# ESQUEMATICO.net
KiCad netlist of a schematic drawn in Altium Designer
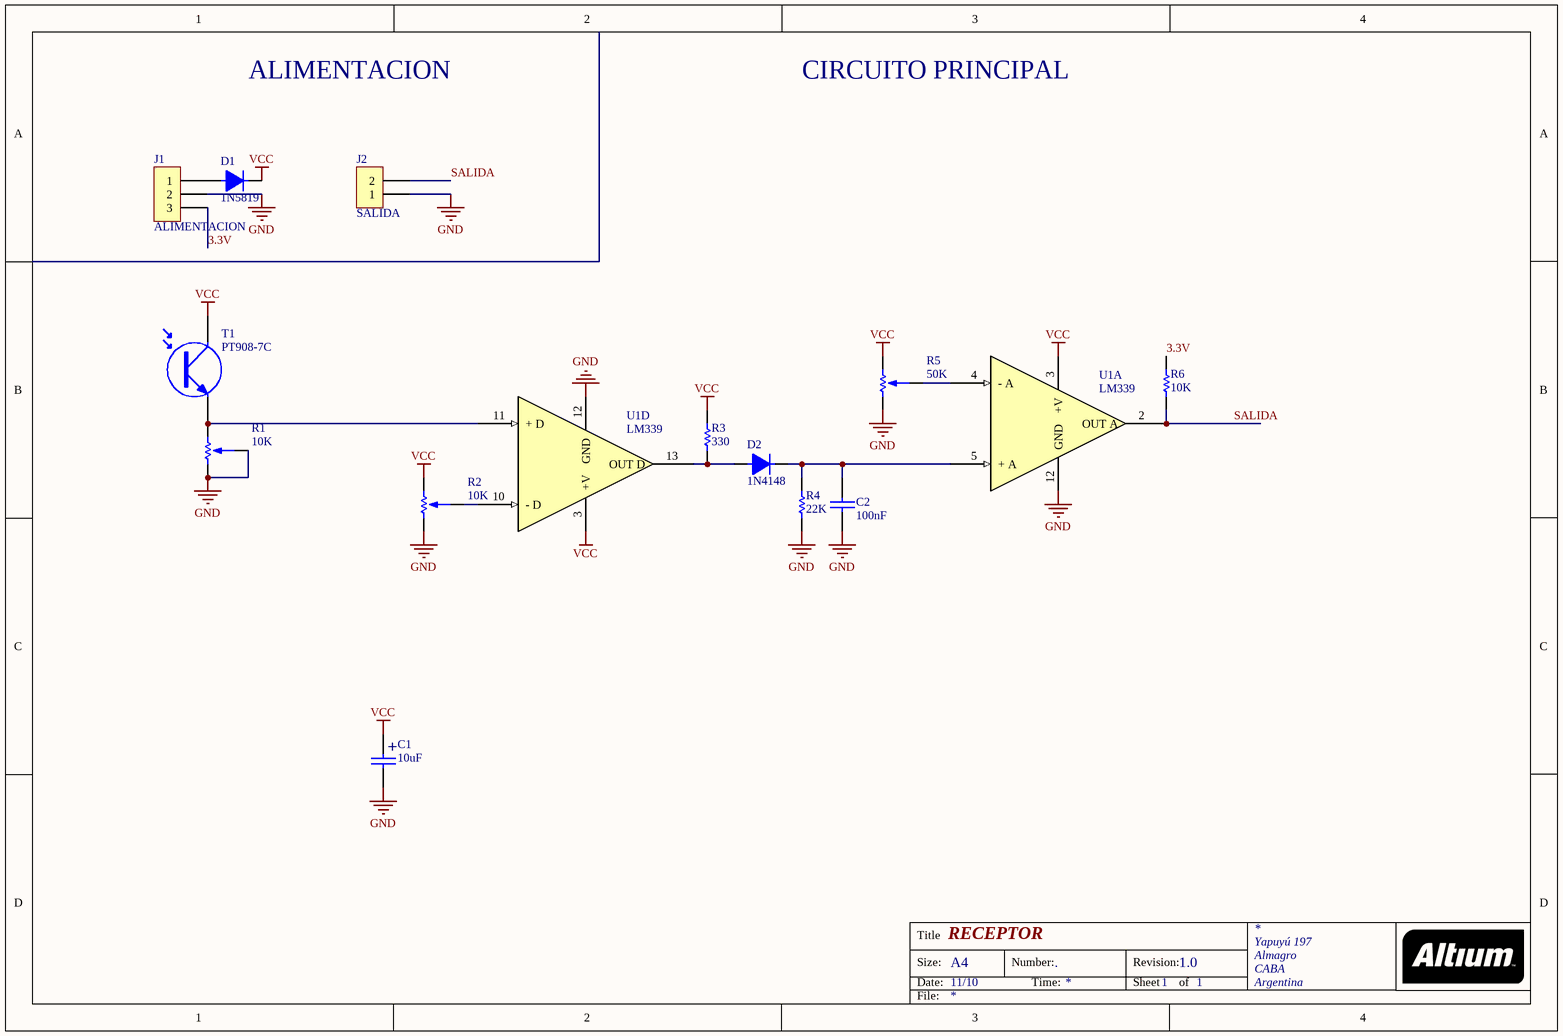
[diagram p0: ESQUEMATICO.SchDoc]

(export (version "E")
  (design (tool "Eeschema 10.0.6"))
  (components
    (comp (ref "C1") (value "10uF") (footprint "CAP100RP") (libsource (lib "LIB-PIO-IX") (part "CAPPOL")))
    (comp (ref "C2") (value "100nF") (footprint "CAP200") (libsource (lib "Libreria4") (part "CAP")))
    (comp (ref "D1") (value "1N5819") (footprint "DO41") (libsource (lib "Libreria4") (part "DIODO")))
    (comp (ref "D2") (value "1N4148") (footprint "DO41") (libsource (lib "Libreria4") (part "DIODO")))
    (comp (ref "J1")
      (value "ALIMENTACION")
      (footprint "BORNERA3")
      (libsource (lib "LIBEBAL") (part "BORNERA 3"))
    )
    (comp (ref "J2") (value "SALIDA") (footprint "BORNERA2") (libsource (lib "Libreria4") (part "BORNERA 2")))
    (comp (ref "R1") (value "10K") (footprint "PRESET V") (libsource (lib "Libreria4") (part "PRESET")))
    (comp (ref "R2") (value "10K") (footprint "PRESET V") (libsource (lib "Libreria4") (part "PRESET")))
    (comp (ref "R3") (value "330") (footprint "RES400") (libsource (lib "Libreria4") (part "RES")))
    (comp (ref "R4") (value "22K") (footprint "RES400") (libsource (lib "Libreria4") (part "RES")))
    (comp (ref "R5") (value "50K") (footprint "PRESET V") (libsource (lib "Libreria4") (part "PRESET")))
    (comp (ref "R6") (value "10K") (footprint "RES400") (libsource (lib "LIBEBAL") (part "RES")))
    (comp (ref "T1")
      (value "PT908-7C")
      (footprint "pototransistor")
      (description "fototransistor")
      (libsource (lib "Libreria4") (part "PT908-7C"))
    )
    (comp (ref "U1")
      (value "LM339")
      (footprint "DIP14")
      (description "Comparador Open Collector")
      (libsource (lib "Libreria4") (part "LM339"))
    )
  )
  (nets
    (net (code "1") (name "/3.3V") (class "Default")
      (node (ref "J1") (pin "3") (pinfunction "3_3") (pintype "passive"))
      (node (ref "R6") (pin "2") (pinfunction "2_2") (pintype "passive"))
    )
    (net (code "2") (name "/SALIDA") (class "Default")
      (node (ref "J2") (pin "2") (pinfunction "2_2") (pintype "passive"))
      (node (ref "R6") (pin "1") (pinfunction "1_1") (pintype "passive"))
      (node (ref "U1") (pin "2") (pinfunction "OUT_A_2") (pintype "open_collector"))
    )
    (net (code "3") (name "GND") (class "Default")
      (node (ref "C1") (pin "2") (pinfunction "2_2") (pintype "passive"))
      (node (ref "C2") (pin "2") (pinfunction "2_2") (pintype "passive"))
      (node (ref "J1") (pin "2") (pinfunction "2_2") (pintype "passive"))
      (node (ref "J2") (pin "1") (pinfunction "1_1") (pintype "passive"))
      (node (ref "R1") (pin "2") (pinfunction "2_2") (pintype "passive"))
      (node (ref "R1") (pin "3") (pinfunction "3_3") (pintype "passive"))
      (node (ref "R2") (pin "3") (pinfunction "3_3") (pintype "passive"))
      (node (ref "R4") (pin "1") (pinfunction "1_1") (pintype "passive"))
      (node (ref "R5") (pin "3") (pinfunction "3_3") (pintype "passive"))
      (node (ref "U1") (pin "12") (pinfunction "GND_12") (pintype "passive"))
    )
    (net (code "4") (name "Net-(D1-Pad1)") (class "Default")
      (node (ref "D1") (pin "1") (pinfunction "1_1") (pintype "passive"))
      (node (ref "J1") (pin "1") (pinfunction "1_1") (pintype "passive"))
    )
    (net (code "5") (name "Net-(T1-E)") (class "Default")
      (node (ref "R1") (pin "1") (pinfunction "1_1") (pintype "passive"))
      (node (ref "T1") (pin "1") (pinfunction "E_1") (pintype "passive"))
      (node (ref "U1") (pin "11") (pinfunction "+_D_11") (pintype "input"))
    )
    (net (code "6") (name "Net-(U1A-+_A)") (class "Default")
      (node (ref "C2") (pin "1") (pinfunction "1_1") (pintype "passive"))
      (node (ref "D2") (pin "2") (pinfunction "2_2") (pintype "passive"))
      (node (ref "R4") (pin "2") (pinfunction "2_2") (pintype "passive"))
      (node (ref "U1") (pin "5") (pinfunction "+_A_5") (pintype "input"))
    )
    (net (code "7") (name "Net-(U1A--_A)") (class "Default")
      (node (ref "R5") (pin "2") (pinfunction "2_2") (pintype "passive"))
      (node (ref "U1") (pin "4") (pinfunction "-_A_4") (pintype "input"))
    )
    (net (code "8") (name "Net-(U1D--_D)") (class "Default")
      (node (ref "R2") (pin "2") (pinfunction "2_2") (pintype "passive"))
      (node (ref "U1") (pin "10") (pinfunction "-_D_10") (pintype "input"))
    )
    (net (code "9") (name "Net-(U1D-OUT_D)") (class "Default")
      (node (ref "D2") (pin "1") (pinfunction "1_1") (pintype "passive"))
      (node (ref "R3") (pin "1") (pinfunction "1_1") (pintype "passive"))
      (node (ref "U1") (pin "13") (pinfunction "OUT_D_13") (pintype "open_collector"))
    )
    (net (code "10") (name "VCC") (class "Default")
      (node (ref "C1") (pin "1") (pinfunction "1_1") (pintype "passive"))
      (node (ref "D1") (pin "2") (pinfunction "2_2") (pintype "passive"))
      (node (ref "R2") (pin "1") (pinfunction "1_1") (pintype "passive"))
      (node (ref "R3") (pin "2") (pinfunction "2_2") (pintype "passive"))
      (node (ref "R5") (pin "1") (pinfunction "1_1") (pintype "passive"))
      (node (ref "T1") (pin "2") (pinfunction "C_2") (pintype "passive"))
      (node (ref "U1") (pin "3") (pinfunction "+V_3") (pintype "passive"))
    )
  )
)
